# Sheet1.net
KiCad netlist of a schematic drawn in Altium Designer
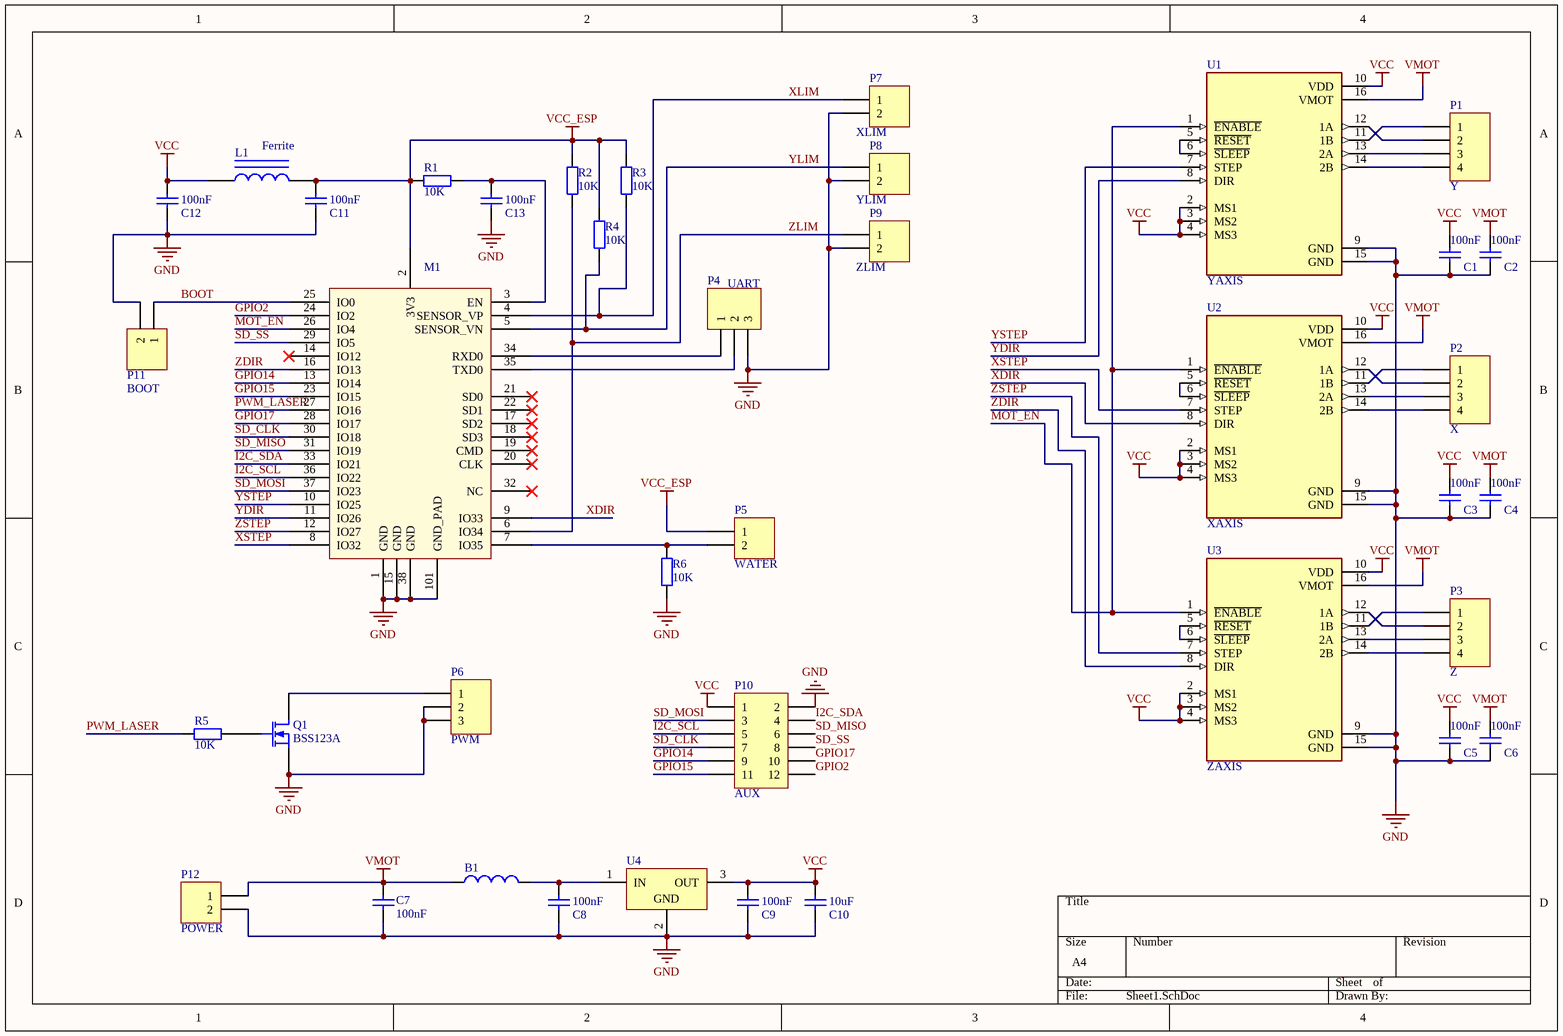
[diagram p0: Sheet1.SchDoc]

(export (version "E")
  (design (tool "Eeschema 10.0.6"))
  (components
    (comp (ref "B1")
      (value "Ferrite")
      (footprint "INDC3225N")
      (description "Inductor")
      (fields (field (name "MANUFACTURER") "Murata"))
      (libsource (lib "Miscellaneous Devices") (part "Inductor"))
    )
    (comp (ref "C1")
      (value "100nF")
      (footprint "0805")
      (description "Capacitor (Semiconductor SIM Model)")
      (fields (field (name "VOLTAGE") "50V") (field (name "MANUFACTURER") "Generic Components"))
      (libsource (lib "Miscellaneous Devices") (part "Cap Semi"))
    )
    (comp (ref "C2")
      (value "100nF")
      (footprint "0805")
      (description "Capacitor (Semiconductor SIM Model)")
      (fields (field (name "VOLTAGE") "50V") (field (name "MANUFACTURER") "Generic Components"))
      (libsource (lib "Miscellaneous Devices") (part "Cap Semi"))
    )
    (comp (ref "C3")
      (value "100nF")
      (footprint "0805")
      (description "Capacitor (Semiconductor SIM Model)")
      (fields (field (name "VOLTAGE") "50V") (field (name "MANUFACTURER") "Generic Components"))
      (libsource (lib "Miscellaneous Devices") (part "Cap Semi"))
    )
    (comp (ref "C4")
      (value "100nF")
      (footprint "0805")
      (description "Capacitor (Semiconductor SIM Model)")
      (fields (field (name "VOLTAGE") "50V") (field (name "MANUFACTURER") "Generic Components"))
      (libsource (lib "Miscellaneous Devices") (part "Cap Semi"))
    )
    (comp (ref "C5")
      (value "100nF")
      (footprint "0805")
      (description "Capacitor (Semiconductor SIM Model)")
      (fields (field (name "VOLTAGE") "50V") (field (name "MANUFACTURER") "Generic Components"))
      (libsource (lib "Miscellaneous Devices") (part "Cap Semi"))
    )
    (comp (ref "C6")
      (value "100nF")
      (footprint "0805")
      (description "Capacitor (Semiconductor SIM Model)")
      (fields (field (name "VOLTAGE") "50V") (field (name "MANUFACTURER") "Generic Components"))
      (libsource (lib "Miscellaneous Devices") (part "Cap Semi"))
    )
    (comp (ref "C7")
      (value "100nF")
      (footprint "0805")
      (description "Capacitor (Semiconductor SIM Model)")
      (fields (field (name "VOLTAGE") "50V") (field (name "MANUFACTURER") "Generic Components"))
      (libsource (lib "Miscellaneous Devices") (part "Cap Semi"))
    )
    (comp (ref "C8")
      (value "100nF")
      (footprint "0805")
      (description "Capacitor (Semiconductor SIM Model)")
      (fields (field (name "VOLTAGE") "50V") (field (name "MANUFACTURER") "Generic Components"))
      (libsource (lib "Miscellaneous Devices") (part "Cap Semi"))
    )
    (comp (ref "C9")
      (value "100nF")
      (footprint "0805")
      (description "Capacitor (Semiconductor SIM Model)")
      (fields (field (name "VOLTAGE") "50V") (field (name "MANUFACTURER") "Generic Components"))
      (libsource (lib "Miscellaneous Devices") (part "Cap Semi"))
    )
    (comp (ref "C10")
      (value "10uF")
      (footprint "1210")
      (description "Capacitor (Semiconductor SIM Model)")
      (fields (field (name "VOLTAGE") "25V") (field (name "MANUFACTURER") "Generic Components"))
      (libsource (lib "Miscellaneous Devices") (part "Cap Semi"))
    )
    (comp (ref "C11")
      (value "100nF")
      (footprint "0805")
      (description "Capacitor (Semiconductor SIM Model)")
      (fields (field (name "VOLTAGE") "50V") (field (name "MANUFACTURER") "Generic Components"))
      (libsource (lib "Miscellaneous Devices") (part "Cap Semi"))
    )
    (comp (ref "C12")
      (value "100nF")
      (footprint "0805")
      (description "Capacitor (Semiconductor SIM Model)")
      (fields (field (name "VOLTAGE") "50V") (field (name "MANUFACTURER") "Generic Components"))
      (libsource (lib "Miscellaneous Devices") (part "Cap Semi"))
    )
    (comp (ref "C13")
      (value "100nF")
      (footprint "0805")
      (description "Capacitor (Semiconductor SIM Model)")
      (fields (field (name "VOLTAGE") "50V") (field (name "MANUFACTURER") "Generic Components"))
      (libsource (lib "Miscellaneous Devices") (part "Cap Semi"))
    )
    (comp (ref "L1")
      (value "Ferrite")
      (footprint "INDC2012N")
      (description "Magnetic-Core Inductor")
      (fields (field (name "MANUFACTURER") "Murata"))
      (libsource (lib "Miscellaneous Devices") (part "Inductor Iron"))
    )
    (comp (ref "M1")
      (value "ESP32S_Module")
      (footprint "ESP32S")
      (description "Esp-32S")
      (libsource (lib "ESP32S") (part "ESP32S_Module"))
    )
    (comp (ref "P1")
      (value "Y")
      (footprint "HDR1X4")
      (description "Header, 4-Pin")
      (fields (field (name "PUBLISHER") "Altium Limited"))
      (libsource (lib "Miscellaneous Connectors") (part "Header 4"))
    )
    (comp (ref "P2")
      (value "X")
      (footprint "HDR1X4")
      (description "Header, 4-Pin")
      (fields (field (name "PUBLISHER") "Altium Limited"))
      (libsource (lib "Miscellaneous Connectors") (part "Header 4"))
    )
    (comp (ref "P3")
      (value "Z")
      (footprint "HDR1X4")
      (description "Header, 4-Pin")
      (fields (field (name "PUBLISHER") "Altium Limited"))
      (libsource (lib "Miscellaneous Connectors") (part "Header 4"))
    )
    (comp (ref "P4")
      (value "UART")
      (footprint "HDR1X3")
      (description "Header, 3-Pin")
      (fields (field (name "PUBLISHER") "Altium Limited"))
      (libsource (lib "") (part "Header 3_1"))
    )
    (comp (ref "P5")
      (value "WATER")
      (footprint "HDR1X2")
      (description "Header, 2-Pin")
      (fields (field (name "PUBLISHER") "Altium Limited"))
      (libsource (lib "Miscellaneous Connectors") (part "Header 2"))
    )
    (comp (ref "P6")
      (value "PWM")
      (footprint "HDR1X3")
      (description "Header, 3-Pin")
      (fields (field (name "PUBLISHER") "Altium Limited"))
      (libsource (lib "Miscellaneous Connectors") (part "Header 3"))
    )
    (comp (ref "P7")
      (value "XLIM")
      (footprint "HDR1X2")
      (description "Header, 2-Pin")
      (fields (field (name "PUBLISHER") "Altium Limited"))
      (libsource (lib "Miscellaneous Connectors") (part "Header 2"))
    )
    (comp (ref "P8")
      (value "YLIM")
      (footprint "HDR1X2")
      (description "Header, 2-Pin")
      (fields (field (name "PUBLISHER") "Altium Limited"))
      (libsource (lib "Miscellaneous Connectors") (part "Header 2"))
    )
    (comp (ref "P9")
      (value "ZLIM")
      (footprint "HDR1X2")
      (description "Header, 2-Pin")
      (fields (field (name "PUBLISHER") "Altium Limited"))
      (libsource (lib "Miscellaneous Connectors") (part "Header 2"))
    )
    (comp (ref "P10")
      (value "AUX")
      (footprint "HDR2X6")
      (description "Header, 6-Pin, Dual row")
      (fields (field (name "PUBLISHER") "Altium Limited"))
      (libsource (lib "Miscellaneous Connectors") (part "Header 6X2"))
    )
    (comp (ref "P11")
      (value "BOOT")
      (footprint "HDR1X2")
      (description "Header, 2-Pin")
      (fields (field (name "PUBLISHER") "Altium Limited"))
      (libsource (lib "") (part "Header 2_1"))
    )
    (comp (ref "P12")
      (value "POWER")
      (footprint "HDR1X2")
      (description "Header, 2-Pin")
      (fields (field (name "PUBLISHER") "Altium Limited"))
      (libsource (lib "") (part "Header 2_1"))
    )
    (comp (ref "Q1")
      (value "BSS123A")
      (footprint "SOT23_M")
      (description "N-Channel Enhancement Mode Vertical DMOS FET")
      (fields (field (name "PUBLISHER") "Altium Limited"))
      (libsource (lib "Zetex Discrete MOSFET") (part "BSS123A"))
    )
    (comp (ref "R1")
      (value "10K")
      (footprint "0805")
      (description "Resistor")
      (fields (field (name "MANUFACTURER") "Generic Components") (field (name "Comment") "Res2"))
      (libsource (lib "") (part "Res2_1"))
    )
    (comp (ref "R2")
      (value "10K")
      (footprint "0805")
      (description "Resistor")
      (fields (field (name "MANUFACTURER") "Generic Components") (field (name "Comment") "Res2"))
      (libsource (lib "Miscellaneous Devices") (part "Res2"))
    )
    (comp (ref "R3")
      (value "10K")
      (footprint "0805")
      (description "Resistor")
      (fields (field (name "MANUFACTURER") "Generic Components") (field (name "Comment") "Res2"))
      (libsource (lib "Miscellaneous Devices") (part "Res2"))
    )
    (comp (ref "R4")
      (value "10K")
      (footprint "0805")
      (description "Resistor")
      (fields (field (name "MANUFACTURER") "Generic Components") (field (name "Comment") "Res2"))
      (libsource (lib "Miscellaneous Devices") (part "Res2"))
    )
    (comp (ref "R5")
      (value "10K")
      (footprint "0805")
      (description "Resistor")
      (fields (field (name "MANUFACTURER") "Generic Components") (field (name "Comment") "Res2"))
      (libsource (lib "") (part "Res2_2"))
    )
    (comp (ref "R6")
      (value "10K")
      (footprint "0805")
      (description "Resistor")
      (fields (field (name "MANUFACTURER") "Generic Components") (field (name "Comment") "Res2"))
      (libsource (lib "Miscellaneous Devices") (part "Res2"))
    )
    (comp (ref "U1")
      (value "YAXIS")
      (footprint "MODULE_A4988_STEPPER_MOTOR_DRIVER_CARRIER")
      (description "Stepper Motor Driver")
      (fields (field (name "MP") "A4988 STEPPER MOTOR DRIVER CARRIER") (field (name "MF") "Pololu"))
      (libsource (lib "A4988_STEPPER_MOTOR_DRIVER_CARRIER") (part "A4988_STEPPER_MOTOR_DRIVER_CARRIER"))
    )
    (comp (ref "U2")
      (value "XAXIS")
      (footprint "MODULE_A4988_STEPPER_MOTOR_DRIVER_CARRIER")
      (description "Stepper Motor Driver")
      (fields (field (name "MP") "A4988 STEPPER MOTOR DRIVER CARRIER") (field (name "MF") "Pololu"))
      (libsource (lib "A4988_STEPPER_MOTOR_DRIVER_CARRIER") (part "A4988_STEPPER_MOTOR_DRIVER_CARRIER"))
    )
    (comp (ref "U3")
      (value "ZAXIS")
      (footprint "MODULE_A4988_STEPPER_MOTOR_DRIVER_CARRIER")
      (description "Stepper Motor Driver")
      (fields (field (name "MP") "A4988 STEPPER MOTOR DRIVER CARRIER") (field (name "MF") "Pololu"))
      (libsource (lib "A4988_STEPPER_MOTOR_DRIVER_CARRIER") (part "A4988_STEPPER_MOTOR_DRIVER_CARRIER"))
    )
    (comp (ref "U4")
      (value "3V3REG")
      (footprint "TRS1-24xx")
      (description "Switching Regulator,18-32Vin,3.3Vout 1A")
      (libsource (lib "Medios") (part "TSR1-2433"))
    )
  )
  (nets
    (net (code "1") (name "/BOOT") (class "Default")
      (node (ref "M1") (pin "25") (pinfunction "IO0_25") (pintype "passive"))
      (node (ref "P11") (pin "1") (pinfunction "1_1") (pintype "passive"))
    )
    (net (code "2") (name "/GPIO2") (class "Default")
      (node (ref "M1") (pin "24") (pinfunction "IO2_24") (pintype "passive"))
      (node (ref "P10") (pin "12") (pinfunction "12_12") (pintype "passive"))
    )
    (net (code "3") (name "/GPIO14") (class "Default")
      (node (ref "M1") (pin "13") (pinfunction "IO14_13") (pintype "passive"))
      (node (ref "P10") (pin "9") (pinfunction "9_9") (pintype "passive"))
    )
    (net (code "4") (name "/GPIO15") (class "Default")
      (node (ref "M1") (pin "23") (pinfunction "IO15_23") (pintype "passive"))
      (node (ref "P10") (pin "11") (pinfunction "11_11") (pintype "passive"))
    )
    (net (code "5") (name "/GPIO17") (class "Default")
      (node (ref "M1") (pin "28") (pinfunction "IO17_28") (pintype "passive"))
      (node (ref "P10") (pin "10") (pinfunction "10_10") (pintype "passive"))
    )
    (net (code "6") (name "/I2C_SCL") (class "Default")
      (node (ref "M1") (pin "36") (pinfunction "IO22_36") (pintype "passive"))
      (node (ref "P10") (pin "5") (pinfunction "5_5") (pintype "passive"))
    )
    (net (code "7") (name "/I2C_SDA") (class "Default")
      (node (ref "M1") (pin "33") (pinfunction "IO21_33") (pintype "passive"))
      (node (ref "P10") (pin "4") (pinfunction "4_4") (pintype "passive"))
    )
    (net (code "8") (name "/MOT_EN") (class "Default")
      (node (ref "M1") (pin "26") (pinfunction "IO4_26") (pintype "passive"))
      (node (ref "U1") (pin "1") (pinfunction "~{ENABLE}_1") (pintype "input"))
      (node (ref "U2") (pin "1") (pinfunction "~{ENABLE}_1") (pintype "input"))
      (node (ref "U3") (pin "1") (pinfunction "~{ENABLE}_1") (pintype "input"))
    )
    (net (code "9") (name "/PWM_LASER") (class "Default")
      (node (ref "M1") (pin "27") (pinfunction "IO16_27") (pintype "passive"))
      (node (ref "R5") (pin "1") (pinfunction "1_1") (pintype "passive"))
    )
    (net (code "10") (name "/SD_CLK") (class "Default")
      (node (ref "M1") (pin "30") (pinfunction "IO18_30") (pintype "passive"))
      (node (ref "P10") (pin "7") (pinfunction "7_7") (pintype "passive"))
    )
    (net (code "11") (name "/SD_MISO") (class "Default")
      (node (ref "M1") (pin "31") (pinfunction "IO19_31") (pintype "passive"))
      (node (ref "P10") (pin "6") (pinfunction "6_6") (pintype "passive"))
    )
    (net (code "12") (name "/SD_MOSI") (class "Default")
      (node (ref "M1") (pin "37") (pinfunction "IO23_37") (pintype "passive"))
      (node (ref "P10") (pin "3") (pinfunction "3_3") (pintype "passive"))
    )
    (net (code "13") (name "/SD_SS") (class "Default")
      (node (ref "M1") (pin "29") (pinfunction "IO5_29") (pintype "passive"))
      (node (ref "P10") (pin "8") (pinfunction "8_8") (pintype "passive"))
    )
    (net (code "14") (name "/XDIR") (class "Default")
      (node (ref "M1") (pin "9") (pinfunction "IO33_9") (pintype "passive"))
      (node (ref "U2") (pin "8") (pinfunction "DIR_8") (pintype "input"))
    )
    (net (code "15") (name "/XLIM") (class "Default")
      (node (ref "M1") (pin "4") (pinfunction "SENSOR_VP_4") (pintype "passive"))
      (node (ref "P7") (pin "1") (pinfunction "1_1") (pintype "passive"))
      (node (ref "R3") (pin "2") (pinfunction "2_2") (pintype "passive"))
    )
    (net (code "16") (name "/XSTEP") (class "Default")
      (node (ref "M1") (pin "8") (pinfunction "IO32_8") (pintype "passive"))
      (node (ref "U2") (pin "7") (pinfunction "STEP_7") (pintype "input"))
    )
    (net (code "17") (name "/YDIR") (class "Default")
      (node (ref "M1") (pin "11") (pinfunction "IO26_11") (pintype "passive"))
      (node (ref "U1") (pin "8") (pinfunction "DIR_8") (pintype "input"))
    )
    (net (code "18") (name "/YLIM") (class "Default")
      (node (ref "M1") (pin "5") (pinfunction "SENSOR_VN_5") (pintype "passive"))
      (node (ref "P8") (pin "1") (pinfunction "1_1") (pintype "passive"))
      (node (ref "R4") (pin "2") (pinfunction "2_2") (pintype "passive"))
    )
    (net (code "19") (name "/YSTEP") (class "Default")
      (node (ref "M1") (pin "10") (pinfunction "IO25_10") (pintype "passive"))
      (node (ref "U1") (pin "7") (pinfunction "STEP_7") (pintype "input"))
    )
    (net (code "20") (name "/ZDIR") (class "Default")
      (node (ref "M1") (pin "16") (pinfunction "IO13_16") (pintype "passive"))
      (node (ref "U3") (pin "8") (pinfunction "DIR_8") (pintype "input"))
    )
    (net (code "21") (name "/ZLIM") (class "Default")
      (node (ref "M1") (pin "6") (pinfunction "IO34_6") (pintype "passive"))
      (node (ref "P9") (pin "1") (pinfunction "1_1") (pintype "passive"))
      (node (ref "R2") (pin "2") (pinfunction "2_2") (pintype "passive"))
    )
    (net (code "22") (name "/ZSTEP") (class "Default")
      (node (ref "M1") (pin "12") (pinfunction "IO27_12") (pintype "passive"))
      (node (ref "U3") (pin "7") (pinfunction "STEP_7") (pintype "input"))
    )
    (net (code "23") (name "GND") (class "Default")
      (node (ref "C1") (pin "2") (pinfunction "2_2") (pintype "passive"))
      (node (ref "C10") (pin "2") (pinfunction "2_2") (pintype "passive"))
      (node (ref "C11") (pin "2") (pinfunction "2_2") (pintype "passive"))
      (node (ref "C12") (pin "2") (pinfunction "2_2") (pintype "passive"))
      (node (ref "C13") (pin "2") (pinfunction "2_2") (pintype "passive"))
      (node (ref "C2") (pin "2") (pinfunction "2_2") (pintype "passive"))
      (node (ref "C3") (pin "2") (pinfunction "2_2") (pintype "passive"))
      (node (ref "C4") (pin "2") (pinfunction "2_2") (pintype "passive"))
      (node (ref "C5") (pin "2") (pinfunction "2_2") (pintype "passive"))
      (node (ref "C6") (pin "2") (pinfunction "2_2") (pintype "passive"))
      (node (ref "C7") (pin "1") (pinfunction "1_1") (pintype "passive"))
      (node (ref "C8") (pin "2") (pinfunction "2_2") (pintype "passive"))
      (node (ref "C9") (pin "2") (pinfunction "2_2") (pintype "passive"))
      (node (ref "M1") (pin "1") (pinfunction "GND_1") (pintype "power_in"))
      (node (ref "M1") (pin "101") (pinfunction "GND_PAD_101") (pintype "power_in"))
      (node (ref "M1") (pin "15") (pinfunction "GND_15") (pintype "power_in"))
      (node (ref "M1") (pin "38") (pinfunction "GND_38") (pintype "power_in"))
      (node (ref "P10") (pin "2") (pinfunction "2_2") (pintype "passive"))
      (node (ref "P11") (pin "2") (pinfunction "2_2") (pintype "passive"))
      (node (ref "P12") (pin "2") (pinfunction "2_2") (pintype "passive"))
      (node (ref "P4") (pin "3") (pinfunction "3_3") (pintype "passive"))
      (node (ref "P6") (pin "2") (pinfunction "2_2") (pintype "passive"))
      (node (ref "P6") (pin "3") (pinfunction "3_3") (pintype "passive"))
      (node (ref "P7") (pin "2") (pinfunction "2_2") (pintype "passive"))
      (node (ref "P8") (pin "2") (pinfunction "2_2") (pintype "passive"))
      (node (ref "P9") (pin "2") (pinfunction "2_2") (pintype "passive"))
      (node (ref "Q1") (pin "2") (pinfunction "S_2") (pintype "passive"))
      (node (ref "R6") (pin "2") (pinfunction "2_2") (pintype "passive"))
      (node (ref "U1") (pin "15") (pinfunction "GND_15") (pintype "power_in"))
      (node (ref "U1") (pin "9") (pinfunction "GND_9") (pintype "power_in"))
      (node (ref "U2") (pin "15") (pinfunction "GND_15") (pintype "power_in"))
      (node (ref "U2") (pin "9") (pinfunction "GND_9") (pintype "power_in"))
      (node (ref "U3") (pin "15") (pinfunction "GND_15") (pintype "power_in"))
      (node (ref "U3") (pin "9") (pinfunction "GND_9") (pintype "power_in"))
      (node (ref "U4") (pin "2") (pinfunction "GND_2") (pintype "power_in"))
    )
    (net (code "24") (name "Net-(M1-EN)") (class "Default")
      (node (ref "C13") (pin "1") (pinfunction "1_1") (pintype "passive"))
      (node (ref "M1") (pin "3") (pinfunction "EN_3") (pintype "power_in"))
      (node (ref "R1") (pin "1") (pinfunction "1_1") (pintype "passive"))
    )
    (net (code "25") (name "Net-(M1-IO35)") (class "Default")
      (node (ref "M1") (pin "7") (pinfunction "IO35_7") (pintype "passive"))
      (node (ref "P5") (pin "2") (pinfunction "2_2") (pintype "passive"))
      (node (ref "R6") (pin "1") (pinfunction "1_1") (pintype "passive"))
    )
    (net (code "26") (name "Net-(M1-RXD0)") (class "Default")
      (node (ref "M1") (pin "34") (pinfunction "RXD0_34") (pintype "passive"))
      (node (ref "P4") (pin "1") (pinfunction "1_1") (pintype "passive"))
    )
    (net (code "27") (name "Net-(M1-TXD0)") (class "Default")
      (node (ref "M1") (pin "35") (pinfunction "TXD0_35") (pintype "passive"))
      (node (ref "P4") (pin "2") (pinfunction "2_2") (pintype "passive"))
    )
    (net (code "28") (name "Net-(Q1-D)") (class "Default")
      (node (ref "P6") (pin "1") (pinfunction "1_1") (pintype "passive"))
      (node (ref "Q1") (pin "1") (pinfunction "D_1") (pintype "passive"))
    )
    (net (code "29") (name "Net-(Q1-G)") (class "Default")
      (node (ref "Q1") (pin "3") (pinfunction "G_3") (pintype "passive"))
      (node (ref "R5") (pin "2") (pinfunction "2_2") (pintype "passive"))
    )
    (net (code "30") (name "Net-(U1-1A)") (class "Default")
      (node (ref "P1") (pin "2") (pinfunction "2_2") (pintype "passive"))
      (node (ref "U1") (pin "12") (pinfunction "1A_12") (pintype "output"))
    )
    (net (code "31") (name "Net-(U1-1B)") (class "Default")
      (node (ref "P1") (pin "1") (pinfunction "1_1") (pintype "passive"))
      (node (ref "U1") (pin "11") (pinfunction "1B_11") (pintype "output"))
    )
    (net (code "32") (name "Net-(U1-2A)") (class "Default")
      (node (ref "P1") (pin "3") (pinfunction "3_3") (pintype "passive"))
      (node (ref "U1") (pin "13") (pinfunction "2A_13") (pintype "output"))
    )
    (net (code "33") (name "Net-(U1-2B)") (class "Default")
      (node (ref "P1") (pin "4") (pinfunction "4_4") (pintype "passive"))
      (node (ref "U1") (pin "14") (pinfunction "2B_14") (pintype "output"))
    )
    (net (code "34") (name "Net-(U1-~{RESET})") (class "Default")
      (node (ref "U1") (pin "5") (pinfunction "~{RESET}_5") (pintype "input"))
      (node (ref "U1") (pin "6") (pinfunction "~{SLEEP}_6") (pintype "input"))
    )
    (net (code "35") (name "Net-(U2-1A)") (class "Default")
      (node (ref "P2") (pin "2") (pinfunction "2_2") (pintype "passive"))
      (node (ref "U2") (pin "12") (pinfunction "1A_12") (pintype "output"))
    )
    (net (code "36") (name "Net-(U2-1B)") (class "Default")
      (node (ref "P2") (pin "1") (pinfunction "1_1") (pintype "passive"))
      (node (ref "U2") (pin "11") (pinfunction "1B_11") (pintype "output"))
    )
    (net (code "37") (name "Net-(U2-2A)") (class "Default")
      (node (ref "P2") (pin "3") (pinfunction "3_3") (pintype "passive"))
      (node (ref "U2") (pin "13") (pinfunction "2A_13") (pintype "output"))
    )
    (net (code "38") (name "Net-(U2-2B)") (class "Default")
      (node (ref "P2") (pin "4") (pinfunction "4_4") (pintype "passive"))
      (node (ref "U2") (pin "14") (pinfunction "2B_14") (pintype "output"))
    )
    (net (code "39") (name "Net-(U2-~{RESET})") (class "Default")
      (node (ref "U2") (pin "5") (pinfunction "~{RESET}_5") (pintype "input"))
      (node (ref "U2") (pin "6") (pinfunction "~{SLEEP}_6") (pintype "input"))
    )
    (net (code "40") (name "Net-(U3-1A)") (class "Default")
      (node (ref "P3") (pin "2") (pinfunction "2_2") (pintype "passive"))
      (node (ref "U3") (pin "12") (pinfunction "1A_12") (pintype "output"))
    )
    (net (code "41") (name "Net-(U3-1B)") (class "Default")
      (node (ref "P3") (pin "1") (pinfunction "1_1") (pintype "passive"))
      (node (ref "U3") (pin "11") (pinfunction "1B_11") (pintype "output"))
    )
    (net (code "42") (name "Net-(U3-2A)") (class "Default")
      (node (ref "P3") (pin "3") (pinfunction "3_3") (pintype "passive"))
      (node (ref "U3") (pin "13") (pinfunction "2A_13") (pintype "output"))
    )
    (net (code "43") (name "Net-(U3-2B)") (class "Default")
      (node (ref "P3") (pin "4") (pinfunction "4_4") (pintype "passive"))
      (node (ref "U3") (pin "14") (pinfunction "2B_14") (pintype "output"))
    )
    (net (code "44") (name "Net-(U3-~{RESET})") (class "Default")
      (node (ref "U3") (pin "5") (pinfunction "~{RESET}_5") (pintype "input"))
      (node (ref "U3") (pin "6") (pinfunction "~{SLEEP}_6") (pintype "input"))
    )
    (net (code "45") (name "Net-(U4-IN)") (class "Default")
      (node (ref "B1") (pin "2") (pinfunction "2_2") (pintype "passive"))
      (node (ref "C8") (pin "1") (pinfunction "1_1") (pintype "passive"))
      (node (ref "U4") (pin "1") (pinfunction "IN_1") (pintype "power_in"))
    )
    (net (code "46") (name "VCC") (class "Default")
      (node (ref "C1") (pin "1") (pinfunction "1_1") (pintype "passive"))
      (node (ref "C10") (pin "1") (pinfunction "1_1") (pintype "passive"))
      (node (ref "C12") (pin "1") (pinfunction "1_1") (pintype "passive"))
      (node (ref "C3") (pin "1") (pinfunction "1_1") (pintype "passive"))
      (node (ref "C5") (pin "1") (pinfunction "1_1") (pintype "passive"))
      (node (ref "C9") (pin "1") (pinfunction "1_1") (pintype "passive"))
      (node (ref "L1") (pin "1") (pinfunction "1_1") (pintype "passive"))
      (node (ref "P10") (pin "1") (pinfunction "1_1") (pintype "passive"))
      (node (ref "U1") (pin "10") (pinfunction "VDD_10") (pintype "power_in"))
      (node (ref "U1") (pin "2") (pinfunction "MS1_2") (pintype "input"))
      (node (ref "U1") (pin "3") (pinfunction "MS2_3") (pintype "input"))
      (node (ref "U1") (pin "4") (pinfunction "MS3_4") (pintype "input"))
      (node (ref "U2") (pin "10") (pinfunction "VDD_10") (pintype "power_in"))
      (node (ref "U2") (pin "2") (pinfunction "MS1_2") (pintype "input"))
      (node (ref "U2") (pin "3") (pinfunction "MS2_3") (pintype "input"))
      (node (ref "U2") (pin "4") (pinfunction "MS3_4") (pintype "input"))
      (node (ref "U3") (pin "10") (pinfunction "VDD_10") (pintype "power_in"))
      (node (ref "U3") (pin "2") (pinfunction "MS1_2") (pintype "input"))
      (node (ref "U3") (pin "3") (pinfunction "MS2_3") (pintype "input"))
      (node (ref "U3") (pin "4") (pinfunction "MS3_4") (pintype "input"))
      (node (ref "U4") (pin "3") (pinfunction "OUT_3") (pintype "power_in"))
    )
    (net (code "47") (name "VCC_ESP") (class "Default")
      (node (ref "C11") (pin "1") (pinfunction "1_1") (pintype "passive"))
      (node (ref "L1") (pin "2") (pinfunction "2_2") (pintype "passive"))
      (node (ref "M1") (pin "2") (pinfunction "3V3_2") (pintype "power_in"))
      (node (ref "P5") (pin "1") (pinfunction "1_1") (pintype "passive"))
      (node (ref "R1") (pin "2") (pinfunction "2_2") (pintype "passive"))
      (node (ref "R2") (pin "1") (pinfunction "1_1") (pintype "passive"))
      (node (ref "R3") (pin "1") (pinfunction "1_1") (pintype "passive"))
      (node (ref "R4") (pin "1") (pinfunction "1_1") (pintype "passive"))
    )
    (net (code "48") (name "VMOT") (class "Default")
      (node (ref "B1") (pin "1") (pinfunction "1_1") (pintype "passive"))
      (node (ref "C2") (pin "1") (pinfunction "1_1") (pintype "passive"))
      (node (ref "C4") (pin "1") (pinfunction "1_1") (pintype "passive"))
      (node (ref "C6") (pin "1") (pinfunction "1_1") (pintype "passive"))
      (node (ref "C7") (pin "2") (pinfunction "2_2") (pintype "passive"))
      (node (ref "P12") (pin "1") (pinfunction "1_1") (pintype "passive"))
      (node (ref "U1") (pin "16") (pinfunction "VMOT_16") (pintype "power_in"))
      (node (ref "U2") (pin "16") (pinfunction "VMOT_16") (pintype "power_in"))
      (node (ref "U3") (pin "16") (pinfunction "VMOT_16") (pintype "power_in"))
    )
    (net (code "49") (name "unconnected-(M1-CLK-Pad20)") (class "Default")
      (node (ref "M1") (pin "20") (pinfunction "CLK_20") (pintype "passive+no_connect"))
    )
    (net (code "50") (name "unconnected-(M1-CMD-Pad19)") (class "Default")
      (node (ref "M1") (pin "19") (pinfunction "CMD_19") (pintype "passive+no_connect"))
    )
    (net (code "51") (name "unconnected-(M1-IO12-Pad14)") (class "Default")
      (node (ref "M1") (pin "14") (pinfunction "IO12_14") (pintype "passive+no_connect"))
    )
    (net (code "52") (name "unconnected-(M1-NC-Pad32)") (class "Default")
      (node (ref "M1") (pin "32") (pinfunction "NC_32") (pintype "passive+no_connect"))
    )
    (net (code "53") (name "unconnected-(M1-SD0-Pad21)") (class "Default")
      (node (ref "M1") (pin "21") (pinfunction "SD0_21") (pintype "passive+no_connect"))
    )
    (net (code "54") (name "unconnected-(M1-SD1-Pad22)") (class "Default")
      (node (ref "M1") (pin "22") (pinfunction "SD1_22") (pintype "passive+no_connect"))
    )
    (net (code "55") (name "unconnected-(M1-SD2-Pad17)") (class "Default")
      (node (ref "M1") (pin "17") (pinfunction "SD2_17") (pintype "passive+no_connect"))
    )
    (net (code "56") (name "unconnected-(M1-SD3-Pad18)") (class "Default")
      (node (ref "M1") (pin "18") (pinfunction "SD3_18") (pintype "passive+no_connect"))
    )
  )
)
